# ALU_Add_Shift.net
KiCad netlist of a schematic drawn in Altium Designer
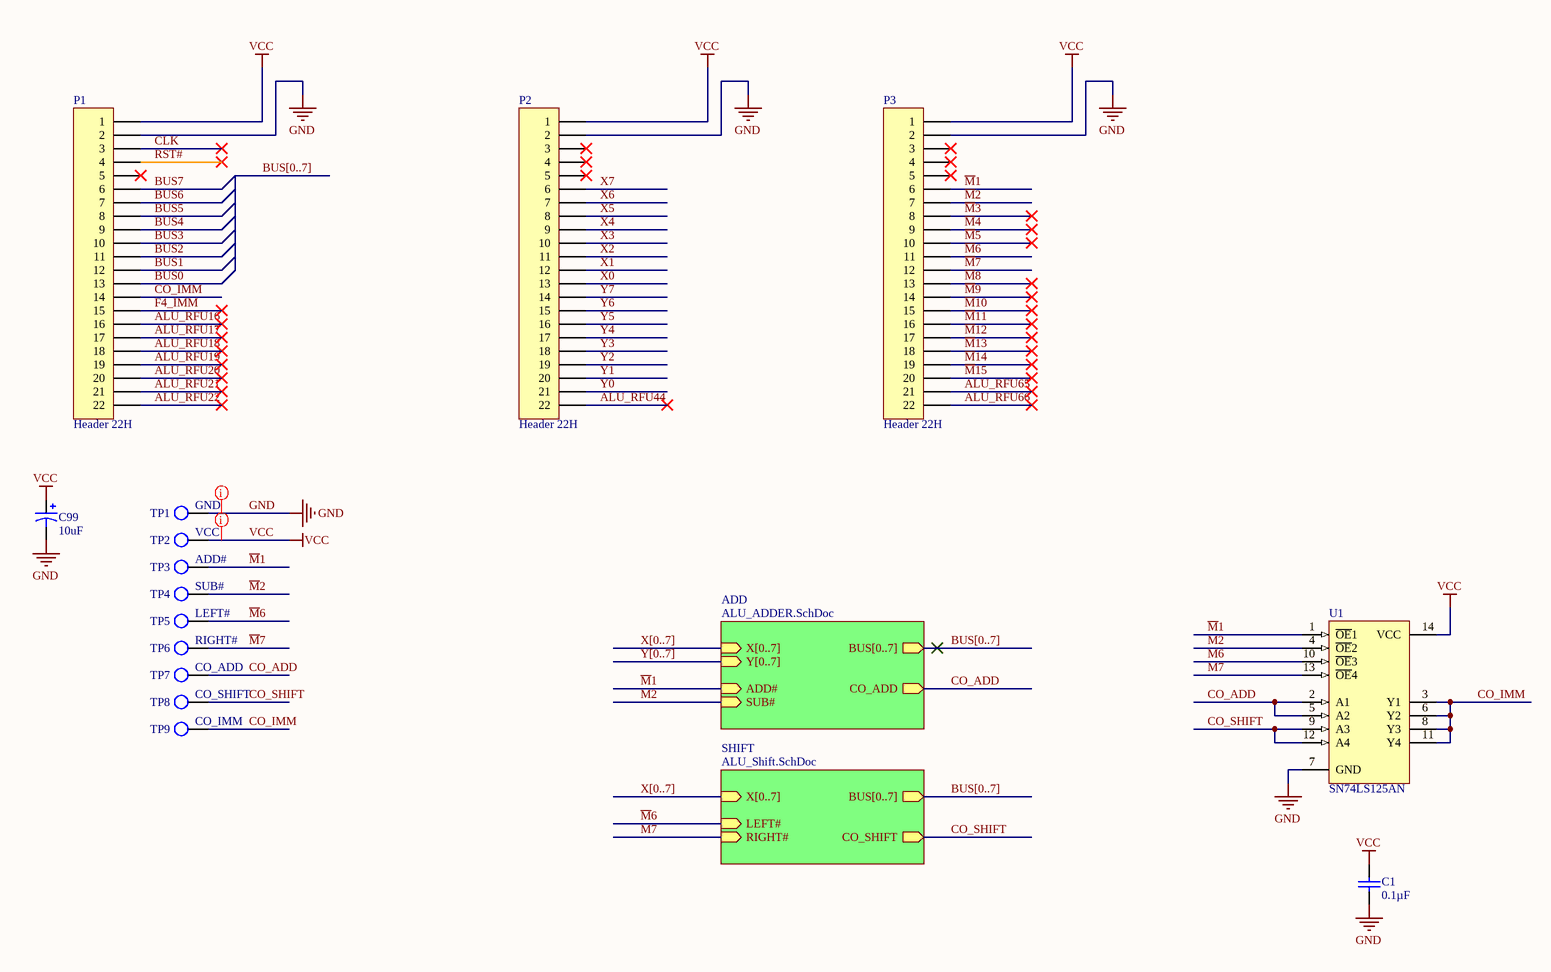
[diagram p0: ALU_Add_Shift.SchDoc]

(export (version "E")
  (design (tool "Eeschema 10.0.6"))
  (components
    (comp (ref "C1")
      (value "K104K15X7RF5TL2")
      (footprint "VISH-K104K15X7RF5TL2")
      (description "Ceramic Capacitor, 100 nF, +/- 10%, 50 V, -55 to 125 degC, 2-Pin THD, RoHS, Tape and Reel")
      (fields
        (field (name "MANUFACTURER") "Vishay")
        (field (name "TOLERANCE") "±10%")
        (field (name "CAPACITANCE") "0.1µF")
      )
      (libsource (lib "Altium Content Vault") (part "CAP-NP-2"))
    )
    (comp (ref "C99")
      (value "10uF")
      (footprint "C5x7")
      (description "Polarized Capacitor")
      (fields (field (name "Comment") "Cap Pol5") (field (name "PUBLISHER") "Altium Limited"))
      (libsource (lib "Miscellaneous Devices") (part "Cap Pol5"))
    )
    (comp (ref "P1")
      (value "Header 22H")
      (footprint "HDR1X22H")
      (description "Header, 22-Pin, Right Angle")
      (fields (field (name "PUBLISHER") "Altium Limited"))
      (libsource (lib "Miscellaneous Connectors") (part "Header 22H"))
    )
    (comp (ref "P2")
      (value "Header 22H")
      (footprint "HDR1X22H")
      (description "Header, 22-Pin, Right Angle")
      (fields (field (name "PUBLISHER") "Altium Limited"))
      (libsource (lib "Miscellaneous Connectors") (part "Header 22H"))
    )
    (comp (ref "P3")
      (value "Header 22H")
      (footprint "HDR1X22H")
      (description "Header, 22-Pin, Right Angle")
      (fields (field (name "PUBLISHER") "Altium Limited"))
      (libsource (lib "Miscellaneous Connectors") (part "Header 22H"))
    )
    (comp (ref "TP1") (value "GND") (footprint "KSTN-5011_V") (libsource (lib "TP") (part "TP")))
    (comp (ref "TP2") (value "VCC") (footprint "KSTN-5011_V") (libsource (lib "TP") (part "TP")))
    (comp (ref "TP3") (value "ADD#") (footprint "KSTN-5011_V") (libsource (lib "TP") (part "TP")))
    (comp (ref "TP4") (value "SUB#") (footprint "KSTN-5011_V") (libsource (lib "TP") (part "TP")))
    (comp (ref "TP5") (value "LEFT#") (footprint "KSTN-5011_V") (libsource (lib "TP") (part "TP")))
    (comp (ref "TP6") (value "RIGHT#") (footprint "KSTN-5011_V") (libsource (lib "TP") (part "TP")))
    (comp (ref "TP7") (value "CO_ADD") (footprint "KSTN-5011_V") (libsource (lib "TP") (part "TP")))
    (comp (ref "TP8") (value "CO_SHIFT") (footprint "KSTN-5011_V") (libsource (lib "TP") (part "TP")))
    (comp (ref "TP9") (value "CO_IMM") (footprint "KSTN-5011_V") (libsource (lib "TP") (part "TP")))
    (comp (ref "U1")
      (value "SN74LS125AN")
      (footprint "N014")
      (description "Quadruple Bus Buffer with 3-State Outputs")
      (fields (field (name "PUBLISHER") "Altium Limited"))
      (libsource (lib "TI Logic Buffer Line Driver") (part "SN74LS125AN"))
    )
  )
  (nets
    (net (code "1") (name "/ALU_RFU16") (class "Default")
      (node (ref "P1") (pin "16") (pinfunction "16_16") (pintype "passive+no_connect"))
    )
    (net (code "2") (name "/ALU_RFU17") (class "Default")
      (node (ref "P1") (pin "17") (pinfunction "17_17") (pintype "passive+no_connect"))
    )
    (net (code "3") (name "/ALU_RFU18") (class "Default")
      (node (ref "P1") (pin "18") (pinfunction "18_18") (pintype "passive+no_connect"))
    )
    (net (code "4") (name "/ALU_RFU19") (class "Default")
      (node (ref "P1") (pin "19") (pinfunction "19_19") (pintype "passive+no_connect"))
    )
    (net (code "5") (name "/ALU_RFU20") (class "Default")
      (node (ref "P1") (pin "20") (pinfunction "20_20") (pintype "passive+no_connect"))
    )
    (net (code "6") (name "/ALU_RFU21") (class "Default")
      (node (ref "P1") (pin "21") (pinfunction "21_21") (pintype "passive+no_connect"))
    )
    (net (code "7") (name "/ALU_RFU22") (class "Default")
      (node (ref "P1") (pin "22") (pinfunction "22_22") (pintype "passive+no_connect"))
    )
    (net (code "8") (name "/ALU_RFU44") (class "Default")
      (node (ref "P2") (pin "22") (pinfunction "22_22") (pintype "passive+no_connect"))
    )
    (net (code "9") (name "/ALU_RFU65") (class "Default")
      (node (ref "P3") (pin "21") (pinfunction "21_21") (pintype "passive+no_connect"))
    )
    (net (code "10") (name "/ALU_RFU66") (class "Default")
      (node (ref "P3") (pin "22") (pinfunction "22_22") (pintype "passive+no_connect"))
    )
    (net (code "11") (name "/BUS0") (class "Default")
      (node (ref "P1") (pin "13") (pinfunction "13_13") (pintype "passive"))
    )
    (net (code "12") (name "/BUS1") (class "Default")
      (node (ref "P1") (pin "12") (pinfunction "12_12") (pintype "passive"))
    )
    (net (code "13") (name "/BUS2") (class "Default")
      (node (ref "P1") (pin "11") (pinfunction "11_11") (pintype "passive"))
    )
    (net (code "14") (name "/BUS3") (class "Default")
      (node (ref "P1") (pin "10") (pinfunction "10_10") (pintype "passive"))
    )
    (net (code "15") (name "/BUS4") (class "Default")
      (node (ref "P1") (pin "9") (pinfunction "9_9") (pintype "passive"))
    )
    (net (code "16") (name "/BUS5") (class "Default")
      (node (ref "P1") (pin "8") (pinfunction "8_8") (pintype "passive"))
    )
    (net (code "17") (name "/BUS6") (class "Default")
      (node (ref "P1") (pin "7") (pinfunction "7_7") (pintype "passive"))
    )
    (net (code "18") (name "/BUS7") (class "Default")
      (node (ref "P1") (pin "6") (pinfunction "6_6") (pintype "passive"))
    )
    (net (code "20") (name "/CLK") (class "Default")
      (node (ref "P1") (pin "3") (pinfunction "3_3") (pintype "passive+no_connect"))
    )
    (net (code "21") (name "/CO_ADD") (class "Default")
      (node (ref "TP7") (pin "1") (pintype "passive"))
      (node (ref "U1") (pin "2") (pinfunction "A1_2") (pintype "input"))
      (node (ref "U1") (pin "5") (pinfunction "A2_5") (pintype "input"))
    )
    (net (code "22") (name "/CO_IMM") (class "Default")
      (node (ref "P1") (pin "14") (pinfunction "14_14") (pintype "passive"))
      (node (ref "TP9") (pin "1") (pintype "passive"))
      (node (ref "U1") (pin "11") (pinfunction "Y4_11") (pintype "tri_state"))
      (node (ref "U1") (pin "3") (pinfunction "Y1_3") (pintype "tri_state"))
      (node (ref "U1") (pin "6") (pinfunction "Y2_6") (pintype "tri_state"))
      (node (ref "U1") (pin "8") (pinfunction "Y3_8") (pintype "tri_state"))
    )
    (net (code "23") (name "/CO_SHIFT") (class "Default")
      (node (ref "TP8") (pin "1") (pintype "passive"))
      (node (ref "U1") (pin "12") (pinfunction "A4_12") (pintype "input"))
      (node (ref "U1") (pin "9") (pinfunction "A3_9") (pintype "input"))
    )
    (net (code "24") (name "/F4_IMM") (class "Default")
      (node (ref "P1") (pin "15") (pinfunction "15_15") (pintype "passive+no_connect"))
    )
    (net (code "25") (name "/RST#") (class "Default")
      (node (ref "P1") (pin "4") (pinfunction "4_4") (pintype "passive+no_connect"))
    )
    (net (code "26") (name "/X0") (class "Default")
      (node (ref "P2") (pin "13") (pinfunction "13_13") (pintype "passive"))
    )
    (net (code "27") (name "/X1") (class "Default")
      (node (ref "P2") (pin "12") (pinfunction "12_12") (pintype "passive"))
    )
    (net (code "28") (name "/X2") (class "Default")
      (node (ref "P2") (pin "11") (pinfunction "11_11") (pintype "passive"))
    )
    (net (code "29") (name "/X3") (class "Default")
      (node (ref "P2") (pin "10") (pinfunction "10_10") (pintype "passive"))
    )
    (net (code "30") (name "/X4") (class "Default")
      (node (ref "P2") (pin "9") (pinfunction "9_9") (pintype "passive"))
    )
    (net (code "31") (name "/X5") (class "Default")
      (node (ref "P2") (pin "8") (pinfunction "8_8") (pintype "passive"))
    )
    (net (code "32") (name "/X6") (class "Default")
      (node (ref "P2") (pin "7") (pinfunction "7_7") (pintype "passive"))
    )
    (net (code "33") (name "/X7") (class "Default")
      (node (ref "P2") (pin "6") (pinfunction "6_6") (pintype "passive"))
    )
    (net (code "35") (name "/Y0") (class "Default")
      (node (ref "P2") (pin "21") (pinfunction "21_21") (pintype "passive"))
    )
    (net (code "36") (name "/Y1") (class "Default")
      (node (ref "P2") (pin "20") (pinfunction "20_20") (pintype "passive"))
    )
    (net (code "37") (name "/Y2") (class "Default")
      (node (ref "P2") (pin "19") (pinfunction "19_19") (pintype "passive"))
    )
    (net (code "38") (name "/Y3") (class "Default")
      (node (ref "P2") (pin "18") (pinfunction "18_18") (pintype "passive"))
    )
    (net (code "39") (name "/Y4") (class "Default")
      (node (ref "P2") (pin "17") (pinfunction "17_17") (pintype "passive"))
    )
    (net (code "40") (name "/Y5") (class "Default")
      (node (ref "P2") (pin "16") (pinfunction "16_16") (pintype "passive"))
    )
    (net (code "41") (name "/Y6") (class "Default")
      (node (ref "P2") (pin "15") (pinfunction "15_15") (pintype "passive"))
    )
    (net (code "42") (name "/Y7") (class "Default")
      (node (ref "P2") (pin "14") (pinfunction "14_14") (pintype "passive"))
    )
    (net (code "44") (name "/~{M}1") (class "Default")
      (node (ref "P3") (pin "6") (pinfunction "6_6") (pintype "passive"))
      (node (ref "TP3") (pin "1") (pintype "passive"))
      (node (ref "U1") (pin "1") (pinfunction "~{OE}1_1") (pintype "input"))
    )
    (net (code "45") (name "/~{M}2") (class "Default")
      (node (ref "P3") (pin "7") (pinfunction "7_7") (pintype "passive"))
      (node (ref "TP4") (pin "1") (pintype "passive"))
      (node (ref "U1") (pin "4") (pinfunction "~{OE}2_4") (pintype "input"))
    )
    (net (code "46") (name "/~{M}3") (class "Default")
      (node (ref "P3") (pin "8") (pinfunction "8_8") (pintype "passive+no_connect"))
    )
    (net (code "47") (name "/~{M}4") (class "Default")
      (node (ref "P3") (pin "9") (pinfunction "9_9") (pintype "passive+no_connect"))
    )
    (net (code "48") (name "/~{M}5") (class "Default")
      (node (ref "P3") (pin "10") (pinfunction "10_10") (pintype "passive+no_connect"))
    )
    (net (code "49") (name "/~{M}6") (class "Default")
      (node (ref "P3") (pin "11") (pinfunction "11_11") (pintype "passive"))
      (node (ref "TP5") (pin "1") (pintype "passive"))
      (node (ref "U1") (pin "10") (pinfunction "~{OE}3_10") (pintype "input"))
    )
    (net (code "50") (name "/~{M}7") (class "Default")
      (node (ref "P3") (pin "12") (pinfunction "12_12") (pintype "passive"))
      (node (ref "TP6") (pin "1") (pintype "passive"))
      (node (ref "U1") (pin "13") (pinfunction "~{OE}4_13") (pintype "input"))
    )
    (net (code "51") (name "/~{M}8") (class "Default")
      (node (ref "P3") (pin "13") (pinfunction "13_13") (pintype "passive+no_connect"))
    )
    (net (code "52") (name "/~{M}9") (class "Default")
      (node (ref "P3") (pin "14") (pinfunction "14_14") (pintype "passive+no_connect"))
    )
    (net (code "53") (name "/~{M}10") (class "Default")
      (node (ref "P3") (pin "15") (pinfunction "15_15") (pintype "passive+no_connect"))
    )
    (net (code "54") (name "/~{M}11") (class "Default")
      (node (ref "P3") (pin "16") (pinfunction "16_16") (pintype "passive+no_connect"))
    )
    (net (code "55") (name "/~{M}12") (class "Default")
      (node (ref "P3") (pin "17") (pinfunction "17_17") (pintype "passive+no_connect"))
    )
    (net (code "56") (name "/~{M}13") (class "Default")
      (node (ref "P3") (pin "18") (pinfunction "18_18") (pintype "passive+no_connect"))
    )
    (net (code "57") (name "/~{M}14") (class "Default")
      (node (ref "P3") (pin "19") (pinfunction "19_19") (pintype "passive+no_connect"))
    )
    (net (code "58") (name "/~{M}15") (class "Default")
      (node (ref "P3") (pin "20") (pinfunction "20_20") (pintype "passive+no_connect"))
    )
    (net (code "59") (name "GND") (class "Default")
      (node (ref "C1") (pin "2") (pinfunction "2_2") (pintype "passive"))
      (node (ref "C99") (pin "2") (pinfunction "2_2") (pintype "passive"))
      (node (ref "P1") (pin "2") (pinfunction "2_2") (pintype "passive"))
      (node (ref "P2") (pin "2") (pinfunction "2_2") (pintype "passive"))
      (node (ref "P3") (pin "2") (pinfunction "2_2") (pintype "passive"))
      (node (ref "TP1") (pin "1") (pintype "passive"))
      (node (ref "U1") (pin "7") (pinfunction "GND_7") (pintype "power_in"))
    )
    (net (code "60") (name "VCC") (class "Default")
      (node (ref "C1") (pin "1") (pinfunction "1_1") (pintype "passive"))
      (node (ref "C99") (pin "1") (pinfunction "1_1") (pintype "passive"))
      (node (ref "P1") (pin "1") (pinfunction "1_1") (pintype "passive"))
      (node (ref "P2") (pin "1") (pinfunction "1_1") (pintype "passive"))
      (node (ref "P3") (pin "1") (pinfunction "1_1") (pintype "passive"))
      (node (ref "TP2") (pin "1") (pintype "passive"))
      (node (ref "U1") (pin "14") (pinfunction "VCC_14") (pintype "power_in"))
    )
    (net (code "61") (name "unconnected-(P1-Pad5)") (class "Default")
      (node (ref "P1") (pin "5") (pinfunction "5_5") (pintype "passive+no_connect"))
    )
    (net (code "62") (name "unconnected-(P2-Pad3)") (class "Default")
      (node (ref "P2") (pin "3") (pinfunction "3_3") (pintype "passive+no_connect"))
    )
    (net (code "63") (name "unconnected-(P2-Pad4)") (class "Default")
      (node (ref "P2") (pin "4") (pinfunction "4_4") (pintype "passive+no_connect"))
    )
    (net (code "64") (name "unconnected-(P2-Pad5)") (class "Default")
      (node (ref "P2") (pin "5") (pinfunction "5_5") (pintype "passive+no_connect"))
    )
    (net (code "65") (name "unconnected-(P3-Pad3)") (class "Default")
      (node (ref "P3") (pin "3") (pinfunction "3_3") (pintype "passive+no_connect"))
    )
    (net (code "66") (name "unconnected-(P3-Pad4)") (class "Default")
      (node (ref "P3") (pin "4") (pinfunction "4_4") (pintype "passive+no_connect"))
    )
    (net (code "67") (name "unconnected-(P3-Pad5)") (class "Default")
      (node (ref "P3") (pin "5") (pinfunction "5_5") (pintype "passive+no_connect"))
    )
  )
)
